# Power_Supply_1.net
KiCad netlist of a schematic drawn in Altium Designer
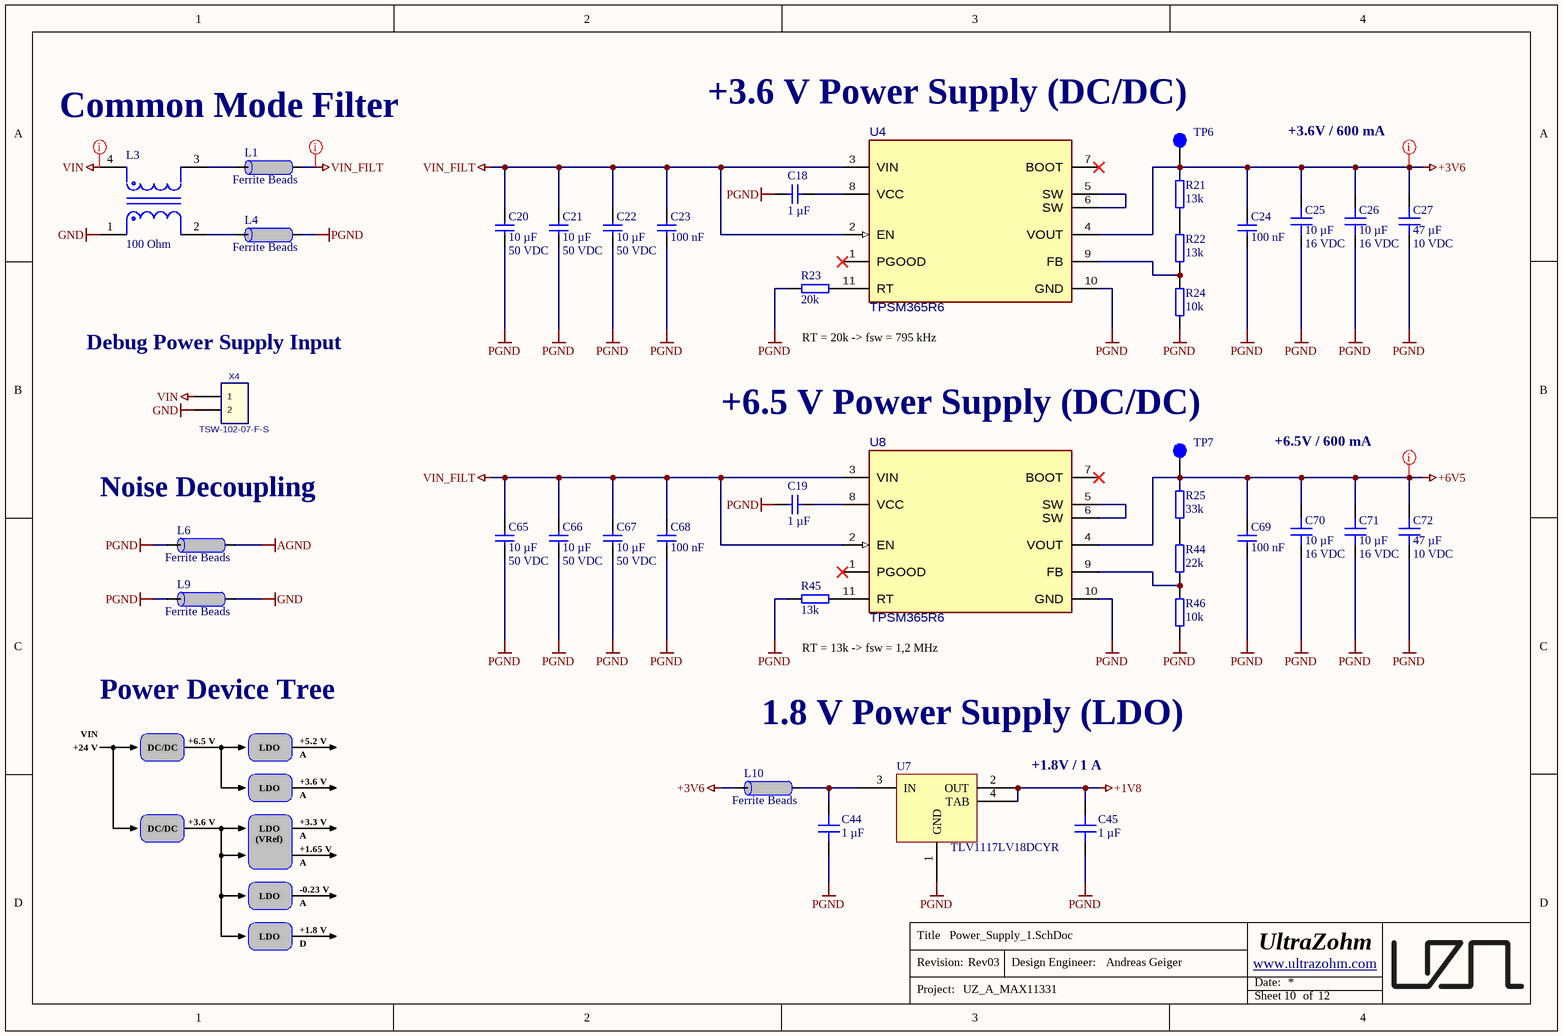
[diagram p0: Power_Supply_1.SchDoc]

(export (version "E")
  (design (tool "Eeschema 10.0.6"))
  (components
    (comp (ref "C18")
      (value "1 µF")
      (footprint "C_0603_TE")
      (description "Generic capacitor")
      (fields
        (field (name "VOLTAGE") "16V")
        (field (name "TOLERANCE") "10 %")
        (field (name "CREATED FROM") "UZgenTool")
      )
      (libsource (lib "user") (part "CAP-NP"))
    )
    (comp (ref "C19")
      (value "1 µF")
      (footprint "C_0603_TE")
      (description "Generic capacitor")
      (fields
        (field (name "VOLTAGE") "16V")
        (field (name "TOLERANCE") "10 %")
        (field (name "CREATED FROM") "UZgenTool")
      )
      (libsource (lib "user") (part "CAP-NP"))
    )
    (comp (ref "C20")
      (value "10 µF")
      (footprint "C_1206_TE")
      (description "50V 10uF X7R ±10% 1206  Multilayer Ceramic Capacitors MLCC - SMD/SMT ROHS")
      (fields
        (field (name "MANUFACTURER PART NUMBER") "CL31B106KBHNNNE")
        (field (name "MANUFACTURER") "Samsung Electro-Mechanics")
        (field (name "VOLTAGE RATING") "50 VDC")
        (field (name "CREATED FROM") "AGeiger")
      )
      (libsource (lib "user") (part "CAP-NP"))
    )
    (comp (ref "C21")
      (value "10 µF")
      (footprint "C_1206_TE")
      (description "50V 10uF X7R ±10% 1206  Multilayer Ceramic Capacitors MLCC - SMD/SMT ROHS")
      (fields
        (field (name "MANUFACTURER PART NUMBER") "CL31B106KBHNNNE")
        (field (name "MANUFACTURER") "Samsung Electro-Mechanics")
        (field (name "VOLTAGE RATING") "50 VDC")
        (field (name "CREATED FROM") "AGeiger")
      )
      (libsource (lib "user") (part "CAP-NP"))
    )
    (comp (ref "C22")
      (value "10 µF")
      (footprint "C_1206_TE")
      (description "50V 10uF X7R ±10% 1206  Multilayer Ceramic Capacitors MLCC - SMD/SMT ROHS")
      (fields
        (field (name "MANUFACTURER PART NUMBER") "CL31B106KBHNNNE")
        (field (name "MANUFACTURER") "Samsung Electro-Mechanics")
        (field (name "VOLTAGE RATING") "50 VDC")
        (field (name "CREATED FROM") "AGeiger")
      )
      (libsource (lib "user") (part "CAP-NP"))
    )
    (comp (ref "C23")
      (value "100 nF")
      (footprint "C_0603_TE")
      (description "Generic capacitor")
      (fields
        (field (name "MANUFACTURER PART NUMBER") "UZgen_C_0603_100nF_50V_X7R")
        (field (name "MANUFACTURER") "UZgen")
        (field (name "CREATED FROM") "AGeiger")
      )
      (libsource (lib "user") (part "CAP-NP"))
    )
    (comp (ref "C24")
      (value "100 nF")
      (footprint "C_0603_TE")
      (description "Generic capacitor")
      (fields
        (field (name "MANUFACTURER PART NUMBER") "UZgen_C_0603_100nF_50V_X7R")
        (field (name "MANUFACTURER") "UZgen")
        (field (name "CREATED FROM") "AGeiger")
      )
      (libsource (lib "user") (part "CAP-NP"))
    )
    (comp (ref "C25")
      (value "10 µF")
      (footprint "C_0603_TE")
      (description "Capacitor 0603, 16 VDC, 10 µF, X5R")
      (fields
        (field (name "MANUFACTURER PART NUMBER") "CL10A106MO8NQNC")
        (field (name "MANUFACTURER") "Samsung Electro-Mechanics")
        (field (name "VOLTAGE RATING") "16 VDC")
        (field (name "CREATED FROM") "AGeiger")
      )
      (libsource (lib "user") (part "Capacitor"))
    )
    (comp (ref "C26")
      (value "10 µF")
      (footprint "C_0603_TE")
      (description "Capacitor 0603, 16 VDC, 10 µF, X5R")
      (fields
        (field (name "MANUFACTURER PART NUMBER") "CL10A106MO8NQNC")
        (field (name "MANUFACTURER") "Samsung Electro-Mechanics")
        (field (name "VOLTAGE RATING") "16 VDC")
        (field (name "CREATED FROM") "AGeiger")
      )
      (libsource (lib "user") (part "Capacitor"))
    )
    (comp (ref "C27")
      (value "47 µF")
      (footprint "C_1210_N")
      (description "10V 47uF X7R ±10% 1210  Multilayer Ceramic Capacitors MLCC - SMD/SMT ROHS")
      (fields
        (field (name "MANUFACTURER PART NUMBER") "GRM32ER71A476KE15L")
        (field (name "MANUFACTURER") "Murata Electronics")
        (field (name "VOLTAGE RATING") "10 VDC")
        (field (name "CREATED FROM") "AGeiger")
      )
      (libsource (lib "user") (part "Capacitor"))
    )
    (comp (ref "C44")
      (value "1 µF")
      (footprint "C_0603")
      (description "50V 1uF X7R ±10% 0603 Multilayer Ceramic Capacitors MLCC - SMD/SMT ROHS")
      (fields
        (field (name "MANUFACTURER PART NUMBER") "UMK107AB7105KA-T")
        (field (name "MANUFACTURER") "Taiyo Yuden")
        (field (name "CREATED FROM") "NDiringer")
      )
      (libsource (lib "user") (part "Capacitor"))
    )
    (comp (ref "C45")
      (value "1 µF")
      (footprint "C_0603")
      (description "50V 1uF X7R ±10% 0603 Multilayer Ceramic Capacitors MLCC - SMD/SMT ROHS")
      (fields
        (field (name "MANUFACTURER PART NUMBER") "UMK107AB7105KA-T")
        (field (name "MANUFACTURER") "Taiyo Yuden")
        (field (name "CREATED FROM") "NDiringer")
      )
      (libsource (lib "user") (part "Capacitor"))
    )
    (comp (ref "C65")
      (value "10 µF")
      (footprint "C_1206_TE")
      (description "50V 10uF X7R ±10% 1206  Multilayer Ceramic Capacitors MLCC - SMD/SMT ROHS")
      (fields
        (field (name "MANUFACTURER PART NUMBER") "CL31B106KBHNNNE")
        (field (name "MANUFACTURER") "Samsung Electro-Mechanics")
        (field (name "VOLTAGE RATING") "50 VDC")
        (field (name "CREATED FROM") "AGeiger")
      )
      (libsource (lib "user") (part "CAP-NP"))
    )
    (comp (ref "C66")
      (value "10 µF")
      (footprint "C_1206_TE")
      (description "50V 10uF X7R ±10% 1206  Multilayer Ceramic Capacitors MLCC - SMD/SMT ROHS")
      (fields
        (field (name "MANUFACTURER PART NUMBER") "CL31B106KBHNNNE")
        (field (name "MANUFACTURER") "Samsung Electro-Mechanics")
        (field (name "VOLTAGE RATING") "50 VDC")
        (field (name "CREATED FROM") "AGeiger")
      )
      (libsource (lib "user") (part "CAP-NP"))
    )
    (comp (ref "C67")
      (value "10 µF")
      (footprint "C_1206_TE")
      (description "50V 10uF X7R ±10% 1206  Multilayer Ceramic Capacitors MLCC - SMD/SMT ROHS")
      (fields
        (field (name "MANUFACTURER PART NUMBER") "CL31B106KBHNNNE")
        (field (name "MANUFACTURER") "Samsung Electro-Mechanics")
        (field (name "VOLTAGE RATING") "50 VDC")
        (field (name "CREATED FROM") "AGeiger")
      )
      (libsource (lib "user") (part "CAP-NP"))
    )
    (comp (ref "C68")
      (value "100 nF")
      (footprint "C_0603_TE")
      (description "Generic capacitor")
      (fields
        (field (name "MANUFACTURER PART NUMBER") "UZgen_C_0603_100nF_50V_X7R")
        (field (name "MANUFACTURER") "UZgen")
        (field (name "CREATED FROM") "AGeiger")
      )
      (libsource (lib "user") (part "CAP-NP"))
    )
    (comp (ref "C69")
      (value "100 nF")
      (footprint "C_0603_TE")
      (description "Generic capacitor")
      (fields
        (field (name "MANUFACTURER PART NUMBER") "UZgen_C_0603_100nF_50V_X7R")
        (field (name "MANUFACTURER") "UZgen")
        (field (name "CREATED FROM") "AGeiger")
      )
      (libsource (lib "user") (part "CAP-NP"))
    )
    (comp (ref "C70")
      (value "10 µF")
      (footprint "C_0603_TE")
      (description "Capacitor 0603, 16 VDC, 10 µF, X5R")
      (fields
        (field (name "MANUFACTURER PART NUMBER") "CL10A106MO8NQNC")
        (field (name "MANUFACTURER") "Samsung Electro-Mechanics")
        (field (name "VOLTAGE RATING") "16 VDC")
        (field (name "CREATED FROM") "AGeiger")
      )
      (libsource (lib "user") (part "Capacitor"))
    )
    (comp (ref "C71")
      (value "10 µF")
      (footprint "C_0603_TE")
      (description "Capacitor 0603, 16 VDC, 10 µF, X5R")
      (fields
        (field (name "MANUFACTURER PART NUMBER") "CL10A106MO8NQNC")
        (field (name "MANUFACTURER") "Samsung Electro-Mechanics")
        (field (name "VOLTAGE RATING") "16 VDC")
        (field (name "CREATED FROM") "AGeiger")
      )
      (libsource (lib "user") (part "Capacitor"))
    )
    (comp (ref "C72")
      (value "47 µF")
      (footprint "C_1210_N")
      (description "10V 47uF X7R ±10% 1210  Multilayer Ceramic Capacitors MLCC - SMD/SMT ROHS")
      (fields
        (field (name "MANUFACTURER PART NUMBER") "GRM32ER71A476KE15L")
        (field (name "MANUFACTURER") "Murata Electronics")
        (field (name "VOLTAGE RATING") "10 VDC")
        (field (name "CREATED FROM") "AGeiger")
      )
      (libsource (lib "user") (part "Capacitor"))
    )
    (comp (ref "L1")
      (value "UPZ2012E601-2R0TF")
      (footprint "INDC2012X92N_V")
      (description "2A 1 90mΩ 600Ω@100MHz ±25% 0805  Ferrite Beads ROHS")
      (fields
        (field (name "COMPONENT TYPE") "Ferrite Beads")
        (field (name "MANUFACTURER") "Sunlord")
        (field (name "LCSC PART NUMBER") "C98308")
        (field (name "CREATED FROM") "AGeiger")
      )
      (libsource (lib "user") (part "Ferrite_Bead"))
    )
    (comp (ref "L3")
      (value "100 Ohm")
      (footprint "FP-DLW5BT-MFG")
      (description "-40℃~125℃ 1.5A 56mΩ 50V 100Ω @ 10MHz 125VDC SMD,5x5mm Common Mode Filters ROHS")
      (fields
        (field (name "MANUFACTURER PART NUMBER") "DLW5BTH142TQ2L")
        (field (name "MANUFACTURER") "Murata")
        (field (name "CREATED FROM") "AGeiger")
      )
      (libsource (lib "user") (part "Common_Mode_Filter"))
    )
    (comp (ref "L4")
      (value "UPZ2012E601-2R0TF")
      (footprint "INDC2012X92N_V")
      (description "2A 1 90mΩ 600Ω@100MHz ±25% 0805  Ferrite Beads ROHS")
      (fields
        (field (name "COMPONENT TYPE") "Ferrite Beads")
        (field (name "MANUFACTURER") "Sunlord")
        (field (name "LCSC PART NUMBER") "C98308")
        (field (name "CREATED FROM") "AGeiger")
      )
      (libsource (lib "user") (part "Ferrite_Bead"))
    )
    (comp (ref "L6")
      (value "UPZ2012E601-2R0TF")
      (footprint "INDC2012X92N_V")
      (description "2A 1 90mΩ 600Ω@100MHz ±25% 0805  Ferrite Beads ROHS")
      (fields
        (field (name "COMPONENT TYPE") "Ferrite Beads")
        (field (name "MANUFACTURER") "Sunlord")
        (field (name "LCSC PART NUMBER") "C98308")
        (field (name "CREATED FROM") "AGeiger")
      )
      (libsource (lib "user") (part "Ferrite_Bead"))
    )
    (comp (ref "L9")
      (value "UPZ2012E601-2R0TF")
      (footprint "INDC2012X92N_V")
      (description "2A 1 90mΩ 600Ω@100MHz ±25% 0805  Ferrite Beads ROHS")
      (fields
        (field (name "COMPONENT TYPE") "Ferrite Beads")
        (field (name "MANUFACTURER") "Sunlord")
        (field (name "LCSC PART NUMBER") "C98308")
        (field (name "CREATED FROM") "AGeiger")
      )
      (libsource (lib "user") (part "Ferrite_Bead"))
    )
    (comp (ref "L10")
      (value "UPZ2012E601-2R0TF")
      (footprint "INDC2012X92N_V")
      (description "2A 1 90mΩ 600Ω@100MHz ±25% 0805  Ferrite Beads ROHS")
      (fields
        (field (name "COMPONENT TYPE") "Ferrite Beads")
        (field (name "MANUFACTURER") "Sunlord")
        (field (name "LCSC PART NUMBER") "C98308")
        (field (name "CREATED FROM") "AGeiger")
      )
      (libsource (lib "user") (part "Ferrite_Bead"))
    )
    (comp (ref "R21")
      (value "13k")
      (footprint "R_0402_TE")
      (description "Generic resistor")
      (fields
        (field (name "MANUFACTURER PART NUMBER") "UZgen_R_0402_13k")
        (field (name "MANUFACTURER") "UZgen")
        (field (name "CREATED FROM") "UZgenTool")
      )
      (libsource (lib "user") (part "RES"))
    )
    (comp (ref "R22")
      (value "13k")
      (footprint "R_0402_TE")
      (description "Generic resistor")
      (fields
        (field (name "MANUFACTURER PART NUMBER") "UZgen_R_0402_13k")
        (field (name "MANUFACTURER") "UZgen")
        (field (name "CREATED FROM") "UZgenTool")
      )
      (libsource (lib "user") (part "RES"))
    )
    (comp (ref "R23")
      (value "20k")
      (footprint "R_0402_TE")
      (description "Generic resistor")
      (fields
        (field (name "MANUFACTURER PART NUMBER") "UZgen_R_0402_20k")
        (field (name "MANUFACTURER") "UZgen")
        (field (name "CREATED FROM") "UZgenTool")
      )
      (libsource (lib "user") (part "RES"))
    )
    (comp (ref "R24")
      (value "10k")
      (footprint "R_0402_TE")
      (description "Generic resistor")
      (fields
        (field (name "MANUFACTURER PART NUMBER") "UZgen_R_0402_10k")
        (field (name "MANUFACTURER") "UZgen")
        (field (name "CREATED FROM") "UZgenTool")
      )
      (libsource (lib "user") (part "RES"))
    )
    (comp (ref "R25")
      (value "33k")
      (footprint "R_0402_TE")
      (description "Generic resistor")
      (fields
        (field (name "MANUFACTURER PART NUMBER") "UZgen_R_0402_33k")
        (field (name "MANUFACTURER") "UZgen")
        (field (name "CREATED FROM") "UZgenTool")
      )
      (libsource (lib "user") (part "RES"))
    )
    (comp (ref "R44")
      (value "22k")
      (footprint "R_0402_TE")
      (description "Generic resistor")
      (fields
        (field (name "MANUFACTURER PART NUMBER") "UZgen_R_0402_22k")
        (field (name "MANUFACTURER") "UZgen")
        (field (name "CREATED FROM") "UZgenTool")
      )
      (libsource (lib "user") (part "RES"))
    )
    (comp (ref "R45")
      (value "13k")
      (footprint "R_0402_TE")
      (description "Generic resistor")
      (fields
        (field (name "MANUFACTURER PART NUMBER") "UZgen_R_0402_13k")
        (field (name "MANUFACTURER") "UZgen")
        (field (name "CREATED FROM") "UZgenTool")
      )
      (libsource (lib "user") (part "RES"))
    )
    (comp (ref "R46")
      (value "10k")
      (footprint "R_0402_TE")
      (description "Generic resistor")
      (fields
        (field (name "MANUFACTURER PART NUMBER") "UZgen_R_0402_10k")
        (field (name "MANUFACTURER") "UZgen")
        (field (name "CREATED FROM") "UZgenTool")
      )
      (libsource (lib "user") (part "RES"))
    )
    (comp (ref "TP6")
      (value "Testpoint 1mm")
      (footprint "TP_1mm")
      (fields
        (field (name "MANUFACTURER PART NUMBER") "Testpoint_1mm")
        (field (name "MANUFACTURER") "UltraZohm")
        (field (name "CREATED") "2018_06_25_AGeiger")
        (field (name "CREATED FROM") "AGeiger")
      )
      (libsource (lib "user") (part "TP_1mm"))
    )
    (comp (ref "TP7")
      (value "Testpoint 1mm")
      (footprint "TP_1mm")
      (fields
        (field (name "MANUFACTURER PART NUMBER") "Testpoint_1mm")
        (field (name "MANUFACTURER") "UltraZohm")
        (field (name "CREATED") "2018_06_25_AGeiger")
        (field (name "CREATED FROM") "AGeiger")
      )
      (libsource (lib "user") (part "TP_1mm"))
    )
    (comp (ref "U4")
      (value "TPSM365R6")
      (footprint "RDN0011A-MFG")
      (description "3-V to 65-V input, 1-V to 13-V output, 0.6-A synchronous buck converter power module")
      (fields
        (field (name "MANUFACTURER PART NUMBER") "TPSM365R6FRDNR")
        (field (name "MANUFACTURER") "Texas Instruments")
        (field (name "CREATED FROM") "AGeiger")
      )
      (libsource (lib "user") (part "TPSM365"))
    )
    (comp (ref "U7")
      (value "TLV1117LV18DCYR")
      (footprint "SOT230P700X170-4N")
      (description "1-A, Positive Fixed-Voltage, Low-Dropout Regulator")
      (fields
        (field (name "MF") "Texas Instruments")
        (field (name "LCSC PART NUMBER") "C80105")
        (field (name "CREATED FROM") "AGeiger")
      )
      (libsource (lib "user") (part "TLV1117LV18DCYR"))
    )
    (comp (ref "U8")
      (value "TPSM365R6")
      (footprint "RDN0011A-MFG")
      (description "3-V to 65-V input, 1-V to 13-V output, 0.6-A synchronous buck converter power module")
      (fields
        (field (name "MANUFACTURER PART NUMBER") "TPSM365R6FRDNR")
        (field (name "MANUFACTURER") "Texas Instruments")
        (field (name "CREATED FROM") "AGeiger")
      )
      (libsource (lib "user") (part "TPSM365"))
    )
    (comp (ref "X4")
      (value "TSW-102-07-F-S")
      (footprint "TSW-102-XX-XXX-S")
      (description "Pin Header, 2.54mm, 2x1")
      (fields
        (field (name "MANUFACTURER") "SAMTEC")
        (field (name "CREATED BY") "May 18, 2016 - Wendy Xin")
        (field (name "CREATED FROM") "AGeiger")
      )
      (libsource (lib "user") (part "TSW-102-XX-XXX-S"))
    )
  )
  (nets
    (net (code "1") (name "+1V8") (class "Default")
      (node (ref "C45") (pin "2") (pinfunction "2_2") (pintype "passive"))
      (node (ref "U7") (pin "2") (pinfunction "OUT_2") (pintype "power_in"))
      (node (ref "U7") (pin "4") (pinfunction "TAB_4") (pintype "power_in"))
    )
    (net (code "2") (name "+3V6") (class "Default")
      (node (ref "C24") (pin "2") (pinfunction "2_2") (pintype "passive"))
      (node (ref "C25") (pin "2") (pinfunction "2_2") (pintype "passive"))
      (node (ref "C26") (pin "2") (pinfunction "2_2") (pintype "passive"))
      (node (ref "C27") (pin "2") (pinfunction "2_2") (pintype "passive"))
      (node (ref "L10") (pin "2") (pinfunction "2_2") (pintype "passive"))
      (node (ref "R21") (pin "2") (pinfunction "2_2") (pintype "passive"))
      (node (ref "TP6") (pin "1") (pintype "passive"))
      (node (ref "U4") (pin "4") (pinfunction "VOUT_4") (pintype "power_in"))
    )
    (net (code "3") (name "+6V5") (class "Default")
      (node (ref "C69") (pin "2") (pinfunction "2_2") (pintype "passive"))
      (node (ref "C70") (pin "2") (pinfunction "2_2") (pintype "passive"))
      (node (ref "C71") (pin "2") (pinfunction "2_2") (pintype "passive"))
      (node (ref "C72") (pin "2") (pinfunction "2_2") (pintype "passive"))
      (node (ref "R25") (pin "2") (pinfunction "2_2") (pintype "passive"))
      (node (ref "TP7") (pin "1") (pintype "passive"))
      (node (ref "U8") (pin "4") (pinfunction "VOUT_4") (pintype "power_in"))
    )
    (net (code "4") (name "AGND") (class "Default")
      (node (ref "L6") (pin "1") (pinfunction "1_1") (pintype "passive"))
    )
    (net (code "5") (name "GND") (class "Default")
      (node (ref "L3") (pin "1") (pinfunction "1_1") (pintype "passive"))
      (node (ref "L9") (pin "1") (pinfunction "1_1") (pintype "passive"))
      (node (ref "X4") (pin "2") (pinfunction "2_2") (pintype "passive"))
    )
    (net (code "6") (name "Net-(L1-Pad2)") (class "Default")
      (node (ref "L1") (pin "2") (pinfunction "2_2") (pintype "passive"))
      (node (ref "L3") (pin "3") (pinfunction "3_3") (pintype "passive"))
    )
    (net (code "7") (name "Net-(L3-Pad2)") (class "Default")
      (node (ref "L3") (pin "2") (pinfunction "2_2") (pintype "passive"))
      (node (ref "L4") (pin "2") (pinfunction "2_2") (pintype "passive"))
    )
    (net (code "8") (name "Net-(R21-Pad1)") (class "Default")
      (node (ref "R21") (pin "1") (pinfunction "1_1") (pintype "passive"))
      (node (ref "R22") (pin "2") (pinfunction "2_2") (pintype "passive"))
    )
    (net (code "9") (name "Net-(R25-Pad1)") (class "Default")
      (node (ref "R25") (pin "1") (pinfunction "1_1") (pintype "passive"))
      (node (ref "R44") (pin "2") (pinfunction "2_2") (pintype "passive"))
    )
    (net (code "10") (name "Net-(U4-FB)") (class "Default")
      (node (ref "R22") (pin "1") (pinfunction "1_1") (pintype "passive"))
      (node (ref "R24") (pin "2") (pinfunction "2_2") (pintype "passive"))
      (node (ref "U4") (pin "9") (pinfunction "FB_9") (pintype "passive"))
    )
    (net (code "11") (name "Net-(U4-RT)") (class "Default")
      (node (ref "R23") (pin "2") (pinfunction "2_2") (pintype "passive"))
      (node (ref "U4") (pin "11") (pinfunction "RT_11") (pintype "passive"))
    )
    (net (code "12") (name "Net-(U4-SW-Pad5)") (class "Default")
      (node (ref "U4") (pin "5") (pinfunction "SW_5") (pintype "passive"))
      (node (ref "U4") (pin "6") (pinfunction "SW_6") (pintype "passive"))
    )
    (net (code "13") (name "Net-(U4-VCC)") (class "Default")
      (node (ref "C18") (pin "2") (pinfunction "2_2") (pintype "passive"))
      (node (ref "U4") (pin "8") (pinfunction "VCC_8") (pintype "power_in"))
    )
    (net (code "14") (name "Net-(U7-IN)") (class "Default")
      (node (ref "C44") (pin "2") (pinfunction "2_2") (pintype "passive"))
      (node (ref "L10") (pin "1") (pinfunction "1_1") (pintype "passive"))
      (node (ref "U7") (pin "3") (pinfunction "IN_3") (pintype "power_in"))
    )
    (net (code "15") (name "Net-(U8-FB)") (class "Default")
      (node (ref "R44") (pin "1") (pinfunction "1_1") (pintype "passive"))
      (node (ref "R46") (pin "2") (pinfunction "2_2") (pintype "passive"))
      (node (ref "U8") (pin "9") (pinfunction "FB_9") (pintype "passive"))
    )
    (net (code "16") (name "Net-(U8-RT)") (class "Default")
      (node (ref "R45") (pin "2") (pinfunction "2_2") (pintype "passive"))
      (node (ref "U8") (pin "11") (pinfunction "RT_11") (pintype "passive"))
    )
    (net (code "17") (name "Net-(U8-SW-Pad5)") (class "Default")
      (node (ref "U8") (pin "5") (pinfunction "SW_5") (pintype "passive"))
      (node (ref "U8") (pin "6") (pinfunction "SW_6") (pintype "passive"))
    )
    (net (code "18") (name "Net-(U8-VCC)") (class "Default")
      (node (ref "C19") (pin "2") (pinfunction "2_2") (pintype "passive"))
      (node (ref "U8") (pin "8") (pinfunction "VCC_8") (pintype "power_in"))
    )
    (net (code "19") (name "PGND") (class "Default")
      (node (ref "C18") (pin "1") (pinfunction "1_1") (pintype "passive"))
      (node (ref "C19") (pin "1") (pinfunction "1_1") (pintype "passive"))
      (node (ref "C20") (pin "2") (pinfunction "2_2") (pintype "passive"))
      (node (ref "C21") (pin "2") (pinfunction "2_2") (pintype "passive"))
      (node (ref "C22") (pin "2") (pinfunction "2_2") (pintype "passive"))
      (node (ref "C23") (pin "1") (pinfunction "1_1") (pintype "passive"))
      (node (ref "C24") (pin "1") (pinfunction "1_1") (pintype "passive"))
      (node (ref "C25") (pin "1") (pinfunction "1_1") (pintype "passive"))
      (node (ref "C26") (pin "1") (pinfunction "1_1") (pintype "passive"))
      (node (ref "C27") (pin "1") (pinfunction "1_1") (pintype "passive"))
      (node (ref "C44") (pin "1") (pinfunction "1_1") (pintype "passive"))
      (node (ref "C45") (pin "1") (pinfunction "1_1") (pintype "passive"))
      (node (ref "C65") (pin "1") (pinfunction "1_1") (pintype "passive"))
      (node (ref "C66") (pin "1") (pinfunction "1_1") (pintype "passive"))
      (node (ref "C67") (pin "1") (pinfunction "1_1") (pintype "passive"))
      (node (ref "C68") (pin "1") (pinfunction "1_1") (pintype "passive"))
      (node (ref "C69") (pin "1") (pinfunction "1_1") (pintype "passive"))
      (node (ref "C70") (pin "1") (pinfunction "1_1") (pintype "passive"))
      (node (ref "C71") (pin "1") (pinfunction "1_1") (pintype "passive"))
      (node (ref "C72") (pin "1") (pinfunction "1_1") (pintype "passive"))
      (node (ref "L4") (pin "1") (pinfunction "1_1") (pintype "passive"))
      (node (ref "L6") (pin "2") (pinfunction "2_2") (pintype "passive"))
      (node (ref "L9") (pin "2") (pinfunction "2_2") (pintype "passive"))
      (node (ref "R23") (pin "1") (pinfunction "1_1") (pintype "passive"))
      (node (ref "R24") (pin "1") (pinfunction "1_1") (pintype "passive"))
      (node (ref "R45") (pin "1") (pinfunction "1_1") (pintype "passive"))
      (node (ref "R46") (pin "1") (pinfunction "1_1") (pintype "passive"))
      (node (ref "U4") (pin "10") (pinfunction "GND_10") (pintype "power_in"))
      (node (ref "U7") (pin "1") (pinfunction "GND_1") (pintype "power_in"))
      (node (ref "U8") (pin "10") (pinfunction "GND_10") (pintype "power_in"))
    )
    (net (code "20") (name "VIN") (class "Default")
      (node (ref "L3") (pin "4") (pinfunction "4_4") (pintype "passive"))
      (node (ref "X4") (pin "1") (pinfunction "1_1") (pintype "passive"))
    )
    (net (code "21") (name "VIN_FILT") (class "Default")
      (node (ref "C20") (pin "1") (pinfunction "1_1") (pintype "passive"))
      (node (ref "C21") (pin "1") (pinfunction "1_1") (pintype "passive"))
      (node (ref "C22") (pin "1") (pinfunction "1_1") (pintype "passive"))
      (node (ref "C23") (pin "2") (pinfunction "2_2") (pintype "passive"))
      (node (ref "C65") (pin "2") (pinfunction "2_2") (pintype "passive"))
      (node (ref "C66") (pin "2") (pinfunction "2_2") (pintype "passive"))
      (node (ref "C67") (pin "2") (pinfunction "2_2") (pintype "passive"))
      (node (ref "C68") (pin "2") (pinfunction "2_2") (pintype "passive"))
      (node (ref "L1") (pin "1") (pinfunction "1_1") (pintype "passive"))
      (node (ref "U4") (pin "2") (pinfunction "EN_2") (pintype "input"))
      (node (ref "U4") (pin "3") (pinfunction "VIN_3") (pintype "power_in"))
      (node (ref "U8") (pin "2") (pinfunction "EN_2") (pintype "input"))
      (node (ref "U8") (pin "3") (pinfunction "VIN_3") (pintype "power_in"))
    )
    (net (code "22") (name "unconnected-(U4-BOOT-Pad7)") (class "Default")
      (node (ref "U4") (pin "7") (pinfunction "BOOT_7") (pintype "passive+no_connect"))
    )
    (net (code "23") (name "unconnected-(U4-PGOOD-Pad1)") (class "Default")
      (node (ref "U4") (pin "1") (pinfunction "PGOOD_1") (pintype "open_collector+no_connect"))
    )
    (net (code "24") (name "unconnected-(U8-BOOT-Pad7)") (class "Default")
      (node (ref "U8") (pin "7") (pinfunction "BOOT_7") (pintype "passive+no_connect"))
    )
    (net (code "25") (name "unconnected-(U8-PGOOD-Pad1)") (class "Default")
      (node (ref "U8") (pin "1") (pinfunction "PGOOD_1") (pintype "open_collector+no_connect"))
    )
  )
)
